# CATS-EUROC-GNSS.net
KiCad netlist of a schematic drawn in Altium Designer
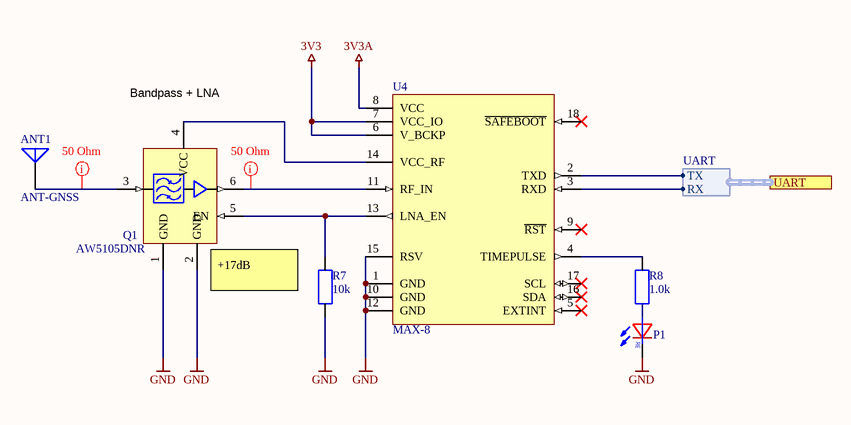
[diagram p0: CATS-EUROC-GNSS.SchDoc]

(export (version "E")
  (design (tool "Eeschema 10.0.6"))
  (components
    (comp (ref "ANT1")
      (value "ANT-GNSS")
      (footprint "THT Antenna GNSS 18x18")
      (description "1.575GHz GPS Ceramic Patch RF Antenna 1.573GHz ~ 1.577GHz 3.3dBic Pin Adhesive")
      (libsource (lib "RF") (part "ANT-GNSS"))
    )
    (comp (ref "P1")
      (value "LED")
      (footprint "SMD LED 0603")
      (description "Color LED")
      (libsource (lib "Diodes") (part "LED"))
    )
    (comp (ref "Q1")
      (value "AW5105DNR")
      (footprint "SMD LNA AW5105DNR")
      (description "BDS/GPS/GNSS INTEGRATED FRONT-END MODULE WITH\r\nLOW NOISE AMPLIFIER AND FILTER")
      (libsource (lib "Analog") (part "AW5105DNR"))
    )
    (comp (ref "R7")
      (value "10k")
      (footprint "SMD Widerstand 0402")
      (description "SMD Chip Resistor E24")
      (libsource (lib "CATS-EUROC") (part "E24 - 10k"))
    )
    (comp (ref "R8")
      (value "1.0k")
      (footprint "SMD Widerstand 0402")
      (description "SMD Chip Resistor E24")
      (libsource (lib "CATS-EUROC") (part "E24 - 1.0k"))
    )
    (comp (ref "U4")
      (value "MAX-8")
      (footprint "SMD MAX-8")
      (description "u-blox 8 GNSS modules")
      (libsource (lib "Sensors") (part "MAX-8"))
    )
  )
  (nets
    (net (code "2") (name "/RX") (class "Default")
      (node (ref "U4") (pin "3") (pinfunction "RXD_3") (pintype "input"))
    )
    (net (code "3") (name "/TX") (class "Default")
      (node (ref "U4") (pin "2") (pinfunction "TXD_2") (pintype "output"))
    )
    (net (code "5") (name "3V3") (class "Default")
      (node (ref "U4") (pin "6") (pinfunction "V_BCKP_6") (pintype "passive"))
      (node (ref "U4") (pin "7") (pinfunction "VCC_IO_7") (pintype "passive"))
    )
    (net (code "6") (name "3V3A") (class "Default")
      (node (ref "U4") (pin "8") (pinfunction "VCC_8") (pintype "passive"))
    )
    (net (code "7") (name "GND") (class "Default")
      (node (ref "P1") (pin "K") (pinfunction "K_K") (pintype "passive"))
      (node (ref "Q1") (pin "1") (pinfunction "GND_1") (pintype "passive"))
      (node (ref "Q1") (pin "2") (pinfunction "GND_2") (pintype "passive"))
      (node (ref "R7") (pin "1") (pinfunction "1_1") (pintype "passive"))
      (node (ref "U4") (pin "1") (pinfunction "GND_1") (pintype "passive"))
      (node (ref "U4") (pin "10") (pinfunction "GND_10") (pintype "passive"))
      (node (ref "U4") (pin "12") (pinfunction "GND_12") (pintype "passive"))
      (node (ref "U4") (pin "15") (pinfunction "RSV_15") (pintype "passive"))
    )
    (net (code "8") (name "Net-(ANT1-Pad1)") (class "Default")
      (node (ref "ANT1") (pin "1") (pinfunction "1_1") (pintype "passive"))
      (node (ref "Q1") (pin "3") (pinfunction "3_3") (pintype "input"))
    )
    (net (code "9") (name "Net-(P1-PadA)") (class "Default")
      (node (ref "P1") (pin "A") (pinfunction "A_A") (pintype "passive"))
      (node (ref "R8") (pin "1") (pinfunction "1_1") (pintype "passive"))
    )
    (net (code "10") (name "Net-(Q1-VCC)") (class "Default")
      (node (ref "Q1") (pin "4") (pinfunction "VCC_4") (pintype "passive"))
      (node (ref "U4") (pin "14") (pinfunction "VCC_RF_14") (pintype "passive"))
    )
    (net (code "11") (name "Net-(U4-LNA_EN)") (class "Default")
      (node (ref "Q1") (pin "5") (pinfunction "EN_5") (pintype "input"))
      (node (ref "R7") (pin "2") (pinfunction "2_2") (pintype "passive"))
      (node (ref "U4") (pin "13") (pinfunction "LNA_EN_13") (pintype "output"))
    )
    (net (code "12") (name "Net-(U4-RF_IN)") (class "Default")
      (node (ref "Q1") (pin "6") (pinfunction "EN_6") (pintype "output"))
      (node (ref "U4") (pin "11") (pinfunction "RF_IN_11") (pintype "input"))
    )
    (net (code "13") (name "Net-(U4-TIMEPULSE)") (class "Default")
      (node (ref "R8") (pin "2") (pinfunction "2_2") (pintype "passive"))
      (node (ref "U4") (pin "4") (pinfunction "TIMEPULSE_4") (pintype "output"))
    )
    (net (code "14") (name "unconnected-(U4-EXTINT-Pad5)") (class "Default")
      (node (ref "U4") (pin "5") (pinfunction "EXTINT_5") (pintype "input+no_connect"))
    )
    (net (code "15") (name "unconnected-(U4-SCL-Pad17)") (class "Default")
      (node (ref "U4") (pin "17") (pinfunction "SCL_17") (pintype "bidirectional+no_connect"))
    )
    (net (code "16") (name "unconnected-(U4-SDA-Pad16)") (class "Default")
      (node (ref "U4") (pin "16") (pinfunction "SDA_16") (pintype "bidirectional+no_connect"))
    )
    (net (code "17") (name "unconnected-(U4-~{RST}-Pad9)") (class "Default")
      (node (ref "U4") (pin "9") (pinfunction "~{RST}_9") (pintype "input+no_connect"))
    )
    (net (code "18") (name "unconnected-(U4-~{SAFEBOOT}-Pad18)") (class "Default")
      (node (ref "U4") (pin "18") (pinfunction "~{SAFEBOOT}_18") (pintype "input+no_connect"))
    )
  )
)
